# FPGA_POWER.net
KiCad netlist of a schematic drawn in Altium Designer
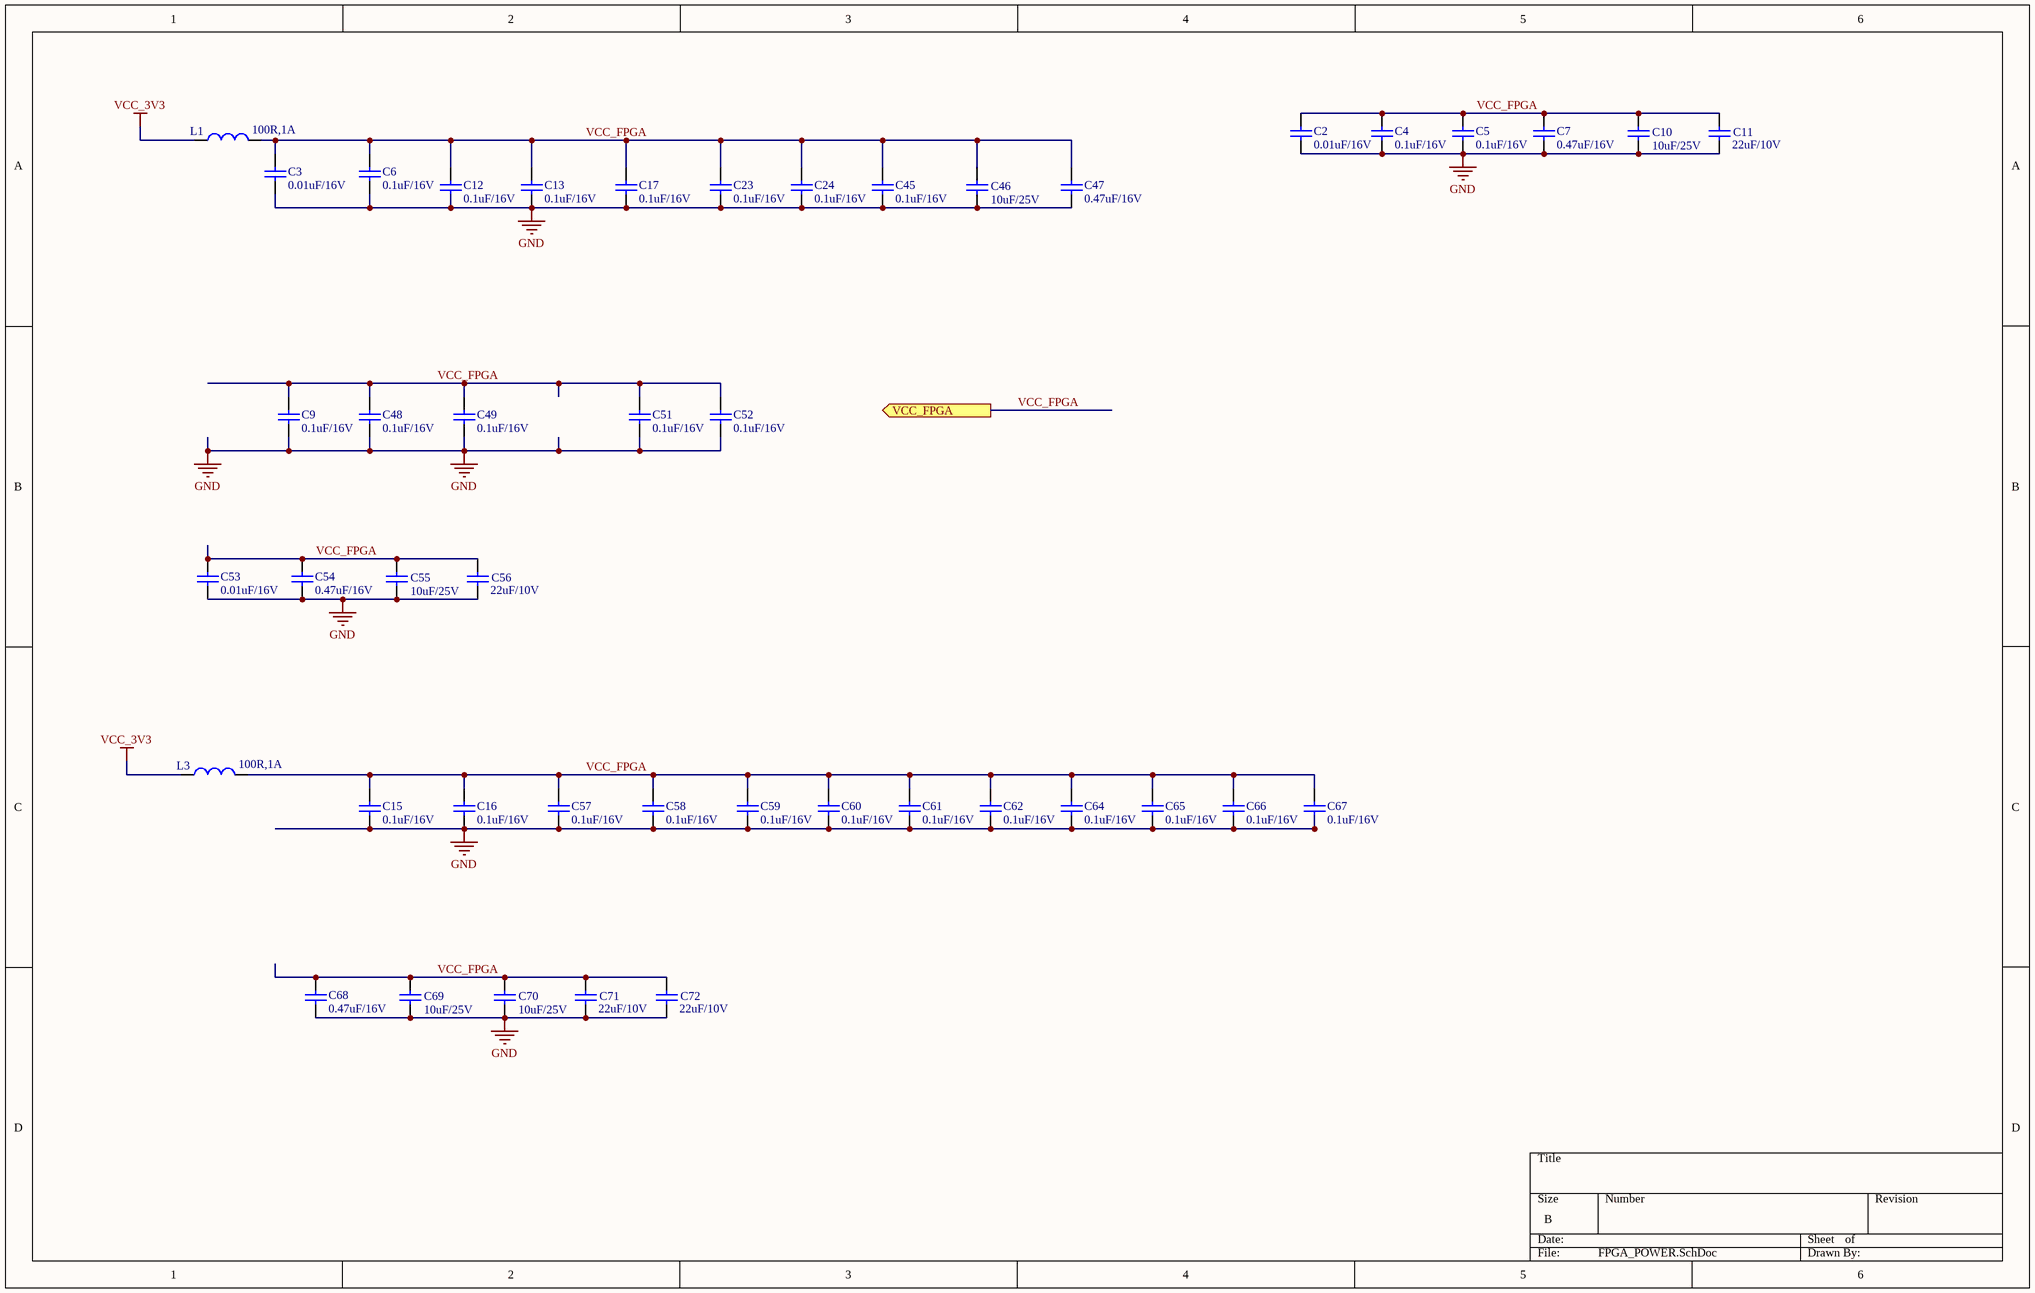
[diagram p0: FPGA_POWER.SchDoc]

(export (version "E")
  (design (tool "Eeschema 10.0.6"))
  (components
    (comp (ref "C2")
      (value "0.01uF/16V")
      (footprint "0603C")
      (description "Multilayer Ceramic Capacitors MLCC - SMD/SMT 16V 0.01uF X7R 0603 10% AEC-Q200")
      (fields (field (name "MFR") "KEMET") (field (name "MFR PART NO") "C0603C103K4RECAUTO"))
      (libsource (lib "Miscellaneous Devices") (part "Cap"))
    )
    (comp (ref "C3")
      (value "0.01uF/16V")
      (footprint "0603C")
      (description "Multilayer Ceramic Capacitors MLCC - SMD/SMT 16V 0.01uF X7R 0603 10% AEC-Q200")
      (fields (field (name "MFR") "KEMET") (field (name "MFR PART NO") "C0603C103K4RECAUTO"))
      (libsource (lib "Miscellaneous Devices") (part "Cap"))
    )
    (comp (ref "C4")
      (value "0.1uF/16V")
      (footprint "0603C")
      (description "Multilayer Ceramic Capacitors MLCC - SMD/SMT 0603 16VDC 0.1uF 10% X7R AEC-Q200")
      (fields (field (name "MFR") "Taiyo Yuden") (field (name "MFR PART NO") "EMK107B7104KAHT"))
      (libsource (lib "Miscellaneous Devices") (part "Cap"))
    )
    (comp (ref "C5")
      (value "0.1uF/16V")
      (footprint "0603C")
      (description "Multilayer Ceramic Capacitors MLCC - SMD/SMT 0603 16VDC 0.1uF 10% X7R AEC-Q200")
      (fields (field (name "MFR") "Taiyo Yuden") (field (name "MFR PART NO") "EMK107B7104KAHT"))
      (libsource (lib "Miscellaneous Devices") (part "Cap"))
    )
    (comp (ref "C6")
      (value "0.1uF/16V")
      (footprint "0603C")
      (description "Multilayer Ceramic Capacitors MLCC - SMD/SMT 0603 16VDC 0.1uF 10% X7R AEC-Q200")
      (fields (field (name "MFR") "Taiyo Yuden") (field (name "MFR PART NO") "EMK107B7104KAHT"))
      (libsource (lib "Miscellaneous Devices") (part "Cap"))
    )
    (comp (ref "C7")
      (value "0.47uF/16V")
      (footprint "0603C")
      (description "Multilayer Ceramic Capacitors MLCC - SMD/SMT 16V 0.47uF 0603 X7R 5% AEC-Q200")
      (fields (field (name "MFR") "KEMET") (field (name "MFR PART NO") "C0603C474J4RACAUTO"))
      (libsource (lib "Miscellaneous Devices") (part "Cap"))
    )
    (comp (ref "C9")
      (value "0.1uF/16V")
      (footprint "0603C")
      (description "Multilayer Ceramic Capacitors MLCC - SMD/SMT 0603 16VDC 0.1uF 10% X7R AEC-Q200")
      (fields (field (name "MFR") "Taiyo Yuden") (field (name "MFR PART NO") "EMK107B7104KAHT"))
      (libsource (lib "Miscellaneous Devices") (part "Cap"))
    )
    (comp (ref "C10")
      (value "10uF/25V")
      (footprint "0805C")
      (description "Multilayer Ceramic Capacitors MLCC - SMD/SMT 0805 25VDC 10uF 20% X5R")
      (fields (field (name "MFR") "Taiyo Yuden") (field (name "MFR PART NO") "TMK212BBJ106MG-T"))
      (libsource (lib "Miscellaneous Devices") (part "Cap"))
    )
    (comp (ref "C11")
      (value "22uF/10V")
      (footprint "0603C")
      (description "Multilayer Ceramic Capacitors MLCC - SMD/SMT 1210 25VDC 22uF 20% X7R AEC-Q200")
      (fields (field (name "MFR") "TDK") (field (name "MFR PART NO") "C1608X5R1A226M080AC"))
      (libsource (lib "Miscellaneous Devices") (part "Cap"))
    )
    (comp (ref "C12")
      (value "0.1uF/16V")
      (footprint "0603C")
      (description "Multilayer Ceramic Capacitors MLCC - SMD/SMT 0603 16VDC 0.1uF 10% X7R AEC-Q200")
      (fields (field (name "MFR") "Taiyo Yuden") (field (name "MFR PART NO") "EMK107B7104KAHT"))
      (libsource (lib "Miscellaneous Devices") (part "Cap"))
    )
    (comp (ref "C13")
      (value "0.1uF/16V")
      (footprint "0603C")
      (description "Multilayer Ceramic Capacitors MLCC - SMD/SMT 0603 16VDC 0.1uF 10% X7R AEC-Q200")
      (fields (field (name "MFR") "Taiyo Yuden") (field (name "MFR PART NO") "EMK107B7104KAHT"))
      (libsource (lib "Miscellaneous Devices") (part "Cap"))
    )
    (comp (ref "C15")
      (value "0.1uF/16V")
      (footprint "0603C")
      (description "Multilayer Ceramic Capacitors MLCC - SMD/SMT 0603 16VDC 0.1uF 10% X7R AEC-Q200")
      (fields (field (name "MFR") "Taiyo Yuden") (field (name "MFR PART NO") "EMK107B7104KAHT"))
      (libsource (lib "Miscellaneous Devices") (part "Cap"))
    )
    (comp (ref "C16")
      (value "0.1uF/16V")
      (footprint "0603C")
      (description "Multilayer Ceramic Capacitors MLCC - SMD/SMT 0603 16VDC 0.1uF 10% X7R AEC-Q200")
      (fields (field (name "MFR") "Taiyo Yuden") (field (name "MFR PART NO") "EMK107B7104KAHT"))
      (libsource (lib "Miscellaneous Devices") (part "Cap"))
    )
    (comp (ref "C17")
      (value "0.1uF/16V")
      (footprint "0603C")
      (description "Multilayer Ceramic Capacitors MLCC - SMD/SMT 0603 16VDC 0.1uF 10% X7R AEC-Q200")
      (fields (field (name "MFR") "Taiyo Yuden") (field (name "MFR PART NO") "EMK107B7104KAHT"))
      (libsource (lib "Miscellaneous Devices") (part "Cap"))
    )
    (comp (ref "C23")
      (value "0.1uF/16V")
      (footprint "0603C")
      (description "Multilayer Ceramic Capacitors MLCC - SMD/SMT 0603 16VDC 0.1uF 10% X7R AEC-Q200")
      (fields (field (name "MFR") "Taiyo Yuden") (field (name "MFR PART NO") "EMK107B7104KAHT"))
      (libsource (lib "Miscellaneous Devices") (part "Cap"))
    )
    (comp (ref "C24")
      (value "0.1uF/16V")
      (footprint "0603C")
      (description "Multilayer Ceramic Capacitors MLCC - SMD/SMT 0603 16VDC 0.1uF 10% X7R AEC-Q200")
      (fields (field (name "MFR") "Taiyo Yuden") (field (name "MFR PART NO") "EMK107B7104KAHT"))
      (libsource (lib "Miscellaneous Devices") (part "Cap"))
    )
    (comp (ref "C45")
      (value "0.1uF/16V")
      (footprint "0603C")
      (description "Multilayer Ceramic Capacitors MLCC - SMD/SMT 0603 16VDC 0.1uF 10% X7R AEC-Q200")
      (fields (field (name "MFR") "Taiyo Yuden") (field (name "MFR PART NO") "EMK107B7104KAHT"))
      (libsource (lib "Miscellaneous Devices") (part "Cap"))
    )
    (comp (ref "C46")
      (value "10uF/25V")
      (footprint "0805C")
      (description "Multilayer Ceramic Capacitors MLCC - SMD/SMT 0805 25VDC 10uF 20% X5R")
      (fields (field (name "MFR") "Taiyo Yuden") (field (name "MFR PART NO") "TMK212BBJ106MG-T"))
      (libsource (lib "Miscellaneous Devices") (part "Cap"))
    )
    (comp (ref "C47")
      (value "0.47uF/16V")
      (footprint "0603C")
      (description "Multilayer Ceramic Capacitors MLCC - SMD/SMT 16V 0.47uF 0603 X7R 5% AEC-Q200")
      (fields (field (name "MFR") "KEMET") (field (name "MFR PART NO") "C0603C474J4RACAUTO"))
      (libsource (lib "Miscellaneous Devices") (part "Cap"))
    )
    (comp (ref "C48")
      (value "0.1uF/16V")
      (footprint "0603C")
      (description "Multilayer Ceramic Capacitors MLCC - SMD/SMT 0603 16VDC 0.1uF 10% X7R AEC-Q200")
      (fields (field (name "MFR") "Taiyo Yuden") (field (name "MFR PART NO") "EMK107B7104KAHT"))
      (libsource (lib "Miscellaneous Devices") (part "Cap"))
    )
    (comp (ref "C49")
      (value "0.1uF/16V")
      (footprint "0603C")
      (description "Multilayer Ceramic Capacitors MLCC - SMD/SMT 0603 16VDC 0.1uF 10% X7R AEC-Q200")
      (fields (field (name "MFR") "Taiyo Yuden") (field (name "MFR PART NO") "EMK107B7104KAHT"))
      (libsource (lib "Miscellaneous Devices") (part "Cap"))
    )
    (comp (ref "C51")
      (value "0.1uF/16V")
      (footprint "0603C")
      (description "Multilayer Ceramic Capacitors MLCC - SMD/SMT 0603 16VDC 0.1uF 10% X7R AEC-Q200")
      (fields (field (name "MFR") "Taiyo Yuden") (field (name "MFR PART NO") "EMK107B7104KAHT"))
      (libsource (lib "Miscellaneous Devices") (part "Cap"))
    )
    (comp (ref "C52")
      (value "0.1uF/16V")
      (footprint "0603C")
      (description "Multilayer Ceramic Capacitors MLCC - SMD/SMT 0603 16VDC 0.1uF 10% X7R AEC-Q200")
      (fields (field (name "MFR") "Taiyo Yuden") (field (name "MFR PART NO") "EMK107B7104KAHT"))
      (libsource (lib "Miscellaneous Devices") (part "Cap"))
    )
    (comp (ref "C53")
      (value "0.01uF/16V")
      (footprint "0603C")
      (description "Multilayer Ceramic Capacitors MLCC - SMD/SMT 16V 0.01uF X7R 0603 10% AEC-Q200")
      (fields (field (name "MFR") "KEMET") (field (name "MFR PART NO") "C0603C103K4RECAUTO"))
      (libsource (lib "Miscellaneous Devices") (part "Cap"))
    )
    (comp (ref "C54")
      (value "0.47uF/16V")
      (footprint "0603C")
      (description "Multilayer Ceramic Capacitors MLCC - SMD/SMT 16V 0.47uF 0603 X7R 5% AEC-Q200")
      (fields (field (name "MFR") "KEMET") (field (name "MFR PART NO") "C0603C474J4RACAUTO"))
      (libsource (lib "Miscellaneous Devices") (part "Cap"))
    )
    (comp (ref "C55")
      (value "10uF/25V")
      (footprint "0805C")
      (description "Multilayer Ceramic Capacitors MLCC - SMD/SMT 0805 25VDC 10uF 20% X5R")
      (fields (field (name "MFR") "Taiyo Yuden") (field (name "MFR PART NO") "TMK212BBJ106MG-T"))
      (libsource (lib "Miscellaneous Devices") (part "Cap"))
    )
    (comp (ref "C56")
      (value "22uF/10V")
      (footprint "0603C")
      (description "Multilayer Ceramic Capacitors MLCC - SMD/SMT 1210 25VDC 22uF 20% X7R AEC-Q200")
      (fields (field (name "MFR") "TDK") (field (name "MFR PART NO") "C1608X5R1A226M080AC"))
      (libsource (lib "Miscellaneous Devices") (part "Cap"))
    )
    (comp (ref "C57")
      (value "0.1uF/16V")
      (footprint "0603C")
      (description "Multilayer Ceramic Capacitors MLCC - SMD/SMT 0603 16VDC 0.1uF 10% X7R AEC-Q200")
      (fields (field (name "MFR") "Taiyo Yuden") (field (name "MFR PART NO") "EMK107B7104KAHT"))
      (libsource (lib "Miscellaneous Devices") (part "Cap"))
    )
    (comp (ref "C58")
      (value "0.1uF/16V")
      (footprint "0603C")
      (description "Multilayer Ceramic Capacitors MLCC - SMD/SMT 0603 16VDC 0.1uF 10% X7R AEC-Q200")
      (fields (field (name "MFR") "Taiyo Yuden") (field (name "MFR PART NO") "EMK107B7104KAHT"))
      (libsource (lib "Miscellaneous Devices") (part "Cap"))
    )
    (comp (ref "C59")
      (value "0.1uF/16V")
      (footprint "0603C")
      (description "Multilayer Ceramic Capacitors MLCC - SMD/SMT 0603 16VDC 0.1uF 10% X7R AEC-Q200")
      (fields (field (name "MFR") "Taiyo Yuden") (field (name "MFR PART NO") "EMK107B7104KAHT"))
      (libsource (lib "Miscellaneous Devices") (part "Cap"))
    )
    (comp (ref "C60")
      (value "0.1uF/16V")
      (footprint "0603C")
      (description "Multilayer Ceramic Capacitors MLCC - SMD/SMT 0603 16VDC 0.1uF 10% X7R AEC-Q200")
      (fields (field (name "MFR") "Taiyo Yuden") (field (name "MFR PART NO") "EMK107B7104KAHT"))
      (libsource (lib "Miscellaneous Devices") (part "Cap"))
    )
    (comp (ref "C61")
      (value "0.1uF/16V")
      (footprint "0603C")
      (description "Multilayer Ceramic Capacitors MLCC - SMD/SMT 0603 16VDC 0.1uF 10% X7R AEC-Q200")
      (fields (field (name "MFR") "Taiyo Yuden") (field (name "MFR PART NO") "EMK107B7104KAHT"))
      (libsource (lib "Miscellaneous Devices") (part "Cap"))
    )
    (comp (ref "C62")
      (value "0.1uF/16V")
      (footprint "0603C")
      (description "Multilayer Ceramic Capacitors MLCC - SMD/SMT 0603 16VDC 0.1uF 10% X7R AEC-Q200")
      (fields (field (name "MFR") "Taiyo Yuden") (field (name "MFR PART NO") "EMK107B7104KAHT"))
      (libsource (lib "Miscellaneous Devices") (part "Cap"))
    )
    (comp (ref "C64")
      (value "0.1uF/16V")
      (footprint "0603C")
      (description "Multilayer Ceramic Capacitors MLCC - SMD/SMT 0603 16VDC 0.1uF 10% X7R AEC-Q200")
      (fields (field (name "MFR") "Taiyo Yuden") (field (name "MFR PART NO") "EMK107B7104KAHT"))
      (libsource (lib "Miscellaneous Devices") (part "Cap"))
    )
    (comp (ref "C65")
      (value "0.1uF/16V")
      (footprint "0603C")
      (description "Multilayer Ceramic Capacitors MLCC - SMD/SMT 0603 16VDC 0.1uF 10% X7R AEC-Q200")
      (fields (field (name "MFR") "Taiyo Yuden") (field (name "MFR PART NO") "EMK107B7104KAHT"))
      (libsource (lib "Miscellaneous Devices") (part "Cap"))
    )
    (comp (ref "C66")
      (value "0.1uF/16V")
      (footprint "0603C")
      (description "Multilayer Ceramic Capacitors MLCC - SMD/SMT 0603 16VDC 0.1uF 10% X7R AEC-Q200")
      (fields (field (name "MFR") "Taiyo Yuden") (field (name "MFR PART NO") "EMK107B7104KAHT"))
      (libsource (lib "Miscellaneous Devices") (part "Cap"))
    )
    (comp (ref "C67")
      (value "0.1uF/16V")
      (footprint "0603C")
      (description "Multilayer Ceramic Capacitors MLCC - SMD/SMT 0603 16VDC 0.1uF 10% X7R AEC-Q200")
      (fields (field (name "MFR") "Taiyo Yuden") (field (name "MFR PART NO") "EMK107B7104KAHT"))
      (libsource (lib "Miscellaneous Devices") (part "Cap"))
    )
    (comp (ref "C68")
      (value "0.47uF/16V")
      (footprint "0603C")
      (description "Multilayer Ceramic Capacitors MLCC - SMD/SMT 16V 0.47uF 0603 X7R 5% AEC-Q200")
      (fields (field (name "MFR") "KEMET") (field (name "MFR PART NO") "C0603C474J4RACAUTO"))
      (libsource (lib "Miscellaneous Devices") (part "Cap"))
    )
    (comp (ref "C69")
      (value "10uF/25V")
      (footprint "0805C")
      (description "Multilayer Ceramic Capacitors MLCC - SMD/SMT 0805 25VDC 10uF 20% X5R")
      (fields (field (name "MFR") "Taiyo Yuden") (field (name "MFR PART NO") "TMK212BBJ106MG-T"))
      (libsource (lib "Miscellaneous Devices") (part "Cap"))
    )
    (comp (ref "C70")
      (value "10uF/25V")
      (footprint "0805C")
      (description "Multilayer Ceramic Capacitors MLCC - SMD/SMT 0805 25VDC 10uF 20% X5R")
      (fields (field (name "MFR") "Taiyo Yuden") (field (name "MFR PART NO") "TMK212BBJ106MG-T"))
      (libsource (lib "Miscellaneous Devices") (part "Cap"))
    )
    (comp (ref "C71")
      (value "22uF/10V")
      (footprint "0603C")
      (description "Multilayer Ceramic Capacitors MLCC - SMD/SMT 1210 25VDC 22uF 20% X7R AEC-Q200")
      (fields (field (name "MFR") "TDK") (field (name "MFR PART NO") "C1608X5R1A226M080AC"))
      (libsource (lib "Miscellaneous Devices") (part "Cap"))
    )
    (comp (ref "C72")
      (value "22uF/10V")
      (footprint "0603C")
      (description "Multilayer Ceramic Capacitors MLCC - SMD/SMT 1210 25VDC 22uF 20% X7R AEC-Q200")
      (fields (field (name "MFR") "TDK") (field (name "MFR PART NO") "C1608X5R1A226M080AC"))
      (libsource (lib "Miscellaneous Devices") (part "Cap"))
    )
    (comp (ref "L1")
      (value "100R,1A")
      (footprint "0603L")
      (description "Ferrite Beads 100ohms 1A 60mOhms 0603 Ferrite Chip")
      (fields (field (name "MFR") "TDK") (field (name "MFR PART NO") "MPZ1608D101BTA00"))
      (libsource (lib "de20") (part "0805_IND"))
    )
    (comp (ref "L3")
      (value "100R,1A")
      (footprint "0603L")
      (description "Ferrite Beads 100ohms 1A 60mOhms 0603 Ferrite Chip")
      (fields (field (name "MFR") "TDK") (field (name "MFR PART NO") "MPZ1608D101BTA00"))
      (libsource (lib "de20") (part "0805_IND"))
    )
  )
  (nets
    (net (code "1") (name "/VCC_FPGA") (class "Default")
      (node (ref "C10") (pin "2") (pinfunction "2_2") (pintype "passive"))
      (node (ref "C11") (pin "2") (pinfunction "2_2") (pintype "passive"))
      (node (ref "C12") (pin "1") (pinfunction "1_1") (pintype "passive"))
      (node (ref "C13") (pin "1") (pinfunction "1_1") (pintype "passive"))
      (node (ref "C15") (pin "1") (pinfunction "1_1") (pintype "passive"))
      (node (ref "C16") (pin "1") (pinfunction "1_1") (pintype "passive"))
      (node (ref "C17") (pin "1") (pinfunction "1_1") (pintype "passive"))
      (node (ref "C2") (pin "1") (pinfunction "1_1") (pintype "passive"))
      (node (ref "C23") (pin "1") (pinfunction "1_1") (pintype "passive"))
      (node (ref "C24") (pin "1") (pinfunction "1_1") (pintype "passive"))
      (node (ref "C3") (pin "1") (pinfunction "1_1") (pintype "passive"))
      (node (ref "C4") (pin "1") (pinfunction "1_1") (pintype "passive"))
      (node (ref "C45") (pin "1") (pinfunction "1_1") (pintype "passive"))
      (node (ref "C46") (pin "2") (pinfunction "2_2") (pintype "passive"))
      (node (ref "C47") (pin "1") (pinfunction "1_1") (pintype "passive"))
      (node (ref "C48") (pin "1") (pinfunction "1_1") (pintype "passive"))
      (node (ref "C49") (pin "1") (pinfunction "1_1") (pintype "passive"))
      (node (ref "C5") (pin "1") (pinfunction "1_1") (pintype "passive"))
      (node (ref "C51") (pin "1") (pinfunction "1_1") (pintype "passive"))
      (node (ref "C52") (pin "1") (pinfunction "1_1") (pintype "passive"))
      (node (ref "C53") (pin "1") (pinfunction "1_1") (pintype "passive"))
      (node (ref "C54") (pin "1") (pinfunction "1_1") (pintype "passive"))
      (node (ref "C55") (pin "2") (pinfunction "2_2") (pintype "passive"))
      (node (ref "C56") (pin "2") (pinfunction "2_2") (pintype "passive"))
      (node (ref "C57") (pin "1") (pinfunction "1_1") (pintype "passive"))
      (node (ref "C58") (pin "1") (pinfunction "1_1") (pintype "passive"))
      (node (ref "C59") (pin "1") (pinfunction "1_1") (pintype "passive"))
      (node (ref "C6") (pin "1") (pinfunction "1_1") (pintype "passive"))
      (node (ref "C60") (pin "1") (pinfunction "1_1") (pintype "passive"))
      (node (ref "C61") (pin "1") (pinfunction "1_1") (pintype "passive"))
      (node (ref "C62") (pin "1") (pinfunction "1_1") (pintype "passive"))
      (node (ref "C64") (pin "1") (pinfunction "1_1") (pintype "passive"))
      (node (ref "C65") (pin "1") (pinfunction "1_1") (pintype "passive"))
      (node (ref "C66") (pin "1") (pinfunction "1_1") (pintype "passive"))
      (node (ref "C67") (pin "1") (pinfunction "1_1") (pintype "passive"))
      (node (ref "C68") (pin "1") (pinfunction "1_1") (pintype "passive"))
      (node (ref "C69") (pin "2") (pinfunction "2_2") (pintype "passive"))
      (node (ref "C7") (pin "1") (pinfunction "1_1") (pintype "passive"))
      (node (ref "C70") (pin "2") (pinfunction "2_2") (pintype "passive"))
      (node (ref "C71") (pin "2") (pinfunction "2_2") (pintype "passive"))
      (node (ref "C72") (pin "2") (pinfunction "2_2") (pintype "passive"))
      (node (ref "C9") (pin "1") (pinfunction "1_1") (pintype "passive"))
      (node (ref "L1") (pin "2") (pinfunction "2_2") (pintype "passive"))
      (node (ref "L3") (pin "2") (pinfunction "2_2") (pintype "passive"))
    )
    (net (code "2") (name "GND") (class "Default")
      (node (ref "C10") (pin "1") (pinfunction "1_1") (pintype "passive"))
      (node (ref "C11") (pin "1") (pinfunction "1_1") (pintype "passive"))
      (node (ref "C12") (pin "2") (pinfunction "2_2") (pintype "passive"))
      (node (ref "C13") (pin "2") (pinfunction "2_2") (pintype "passive"))
      (node (ref "C15") (pin "2") (pinfunction "2_2") (pintype "passive"))
      (node (ref "C16") (pin "2") (pinfunction "2_2") (pintype "passive"))
      (node (ref "C17") (pin "2") (pinfunction "2_2") (pintype "passive"))
      (node (ref "C2") (pin "2") (pinfunction "2_2") (pintype "passive"))
      (node (ref "C23") (pin "2") (pinfunction "2_2") (pintype "passive"))
      (node (ref "C24") (pin "2") (pinfunction "2_2") (pintype "passive"))
      (node (ref "C3") (pin "2") (pinfunction "2_2") (pintype "passive"))
      (node (ref "C4") (pin "2") (pinfunction "2_2") (pintype "passive"))
      (node (ref "C45") (pin "2") (pinfunction "2_2") (pintype "passive"))
      (node (ref "C46") (pin "1") (pinfunction "1_1") (pintype "passive"))
      (node (ref "C47") (pin "2") (pinfunction "2_2") (pintype "passive"))
      (node (ref "C48") (pin "2") (pinfunction "2_2") (pintype "passive"))
      (node (ref "C49") (pin "2") (pinfunction "2_2") (pintype "passive"))
      (node (ref "C5") (pin "2") (pinfunction "2_2") (pintype "passive"))
      (node (ref "C51") (pin "2") (pinfunction "2_2") (pintype "passive"))
      (node (ref "C52") (pin "2") (pinfunction "2_2") (pintype "passive"))
      (node (ref "C53") (pin "2") (pinfunction "2_2") (pintype "passive"))
      (node (ref "C54") (pin "2") (pinfunction "2_2") (pintype "passive"))
      (node (ref "C55") (pin "1") (pinfunction "1_1") (pintype "passive"))
      (node (ref "C56") (pin "1") (pinfunction "1_1") (pintype "passive"))
      (node (ref "C57") (pin "2") (pinfunction "2_2") (pintype "passive"))
      (node (ref "C58") (pin "2") (pinfunction "2_2") (pintype "passive"))
      (node (ref "C59") (pin "2") (pinfunction "2_2") (pintype "passive"))
      (node (ref "C6") (pin "2") (pinfunction "2_2") (pintype "passive"))
      (node (ref "C60") (pin "2") (pinfunction "2_2") (pintype "passive"))
      (node (ref "C61") (pin "2") (pinfunction "2_2") (pintype "passive"))
      (node (ref "C62") (pin "2") (pinfunction "2_2") (pintype "passive"))
      (node (ref "C64") (pin "2") (pinfunction "2_2") (pintype "passive"))
      (node (ref "C65") (pin "2") (pinfunction "2_2") (pintype "passive"))
      (node (ref "C66") (pin "2") (pinfunction "2_2") (pintype "passive"))
      (node (ref "C67") (pin "2") (pinfunction "2_2") (pintype "passive"))
      (node (ref "C68") (pin "2") (pinfunction "2_2") (pintype "passive"))
      (node (ref "C69") (pin "1") (pinfunction "1_1") (pintype "passive"))
      (node (ref "C7") (pin "2") (pinfunction "2_2") (pintype "passive"))
      (node (ref "C70") (pin "1") (pinfunction "1_1") (pintype "passive"))
      (node (ref "C71") (pin "1") (pinfunction "1_1") (pintype "passive"))
      (node (ref "C72") (pin "1") (pinfunction "1_1") (pintype "passive"))
      (node (ref "C9") (pin "2") (pinfunction "2_2") (pintype "passive"))
    )
    (net (code "3") (name "VCC_3V3") (class "Default")
      (node (ref "L1") (pin "1") (pinfunction "1_1") (pintype "passive"))
      (node (ref "L3") (pin "1") (pinfunction "1_1") (pintype "passive"))
    )
  )
)
